# Gas_Sensor.net
KiCad netlist of a schematic drawn in EAGLE
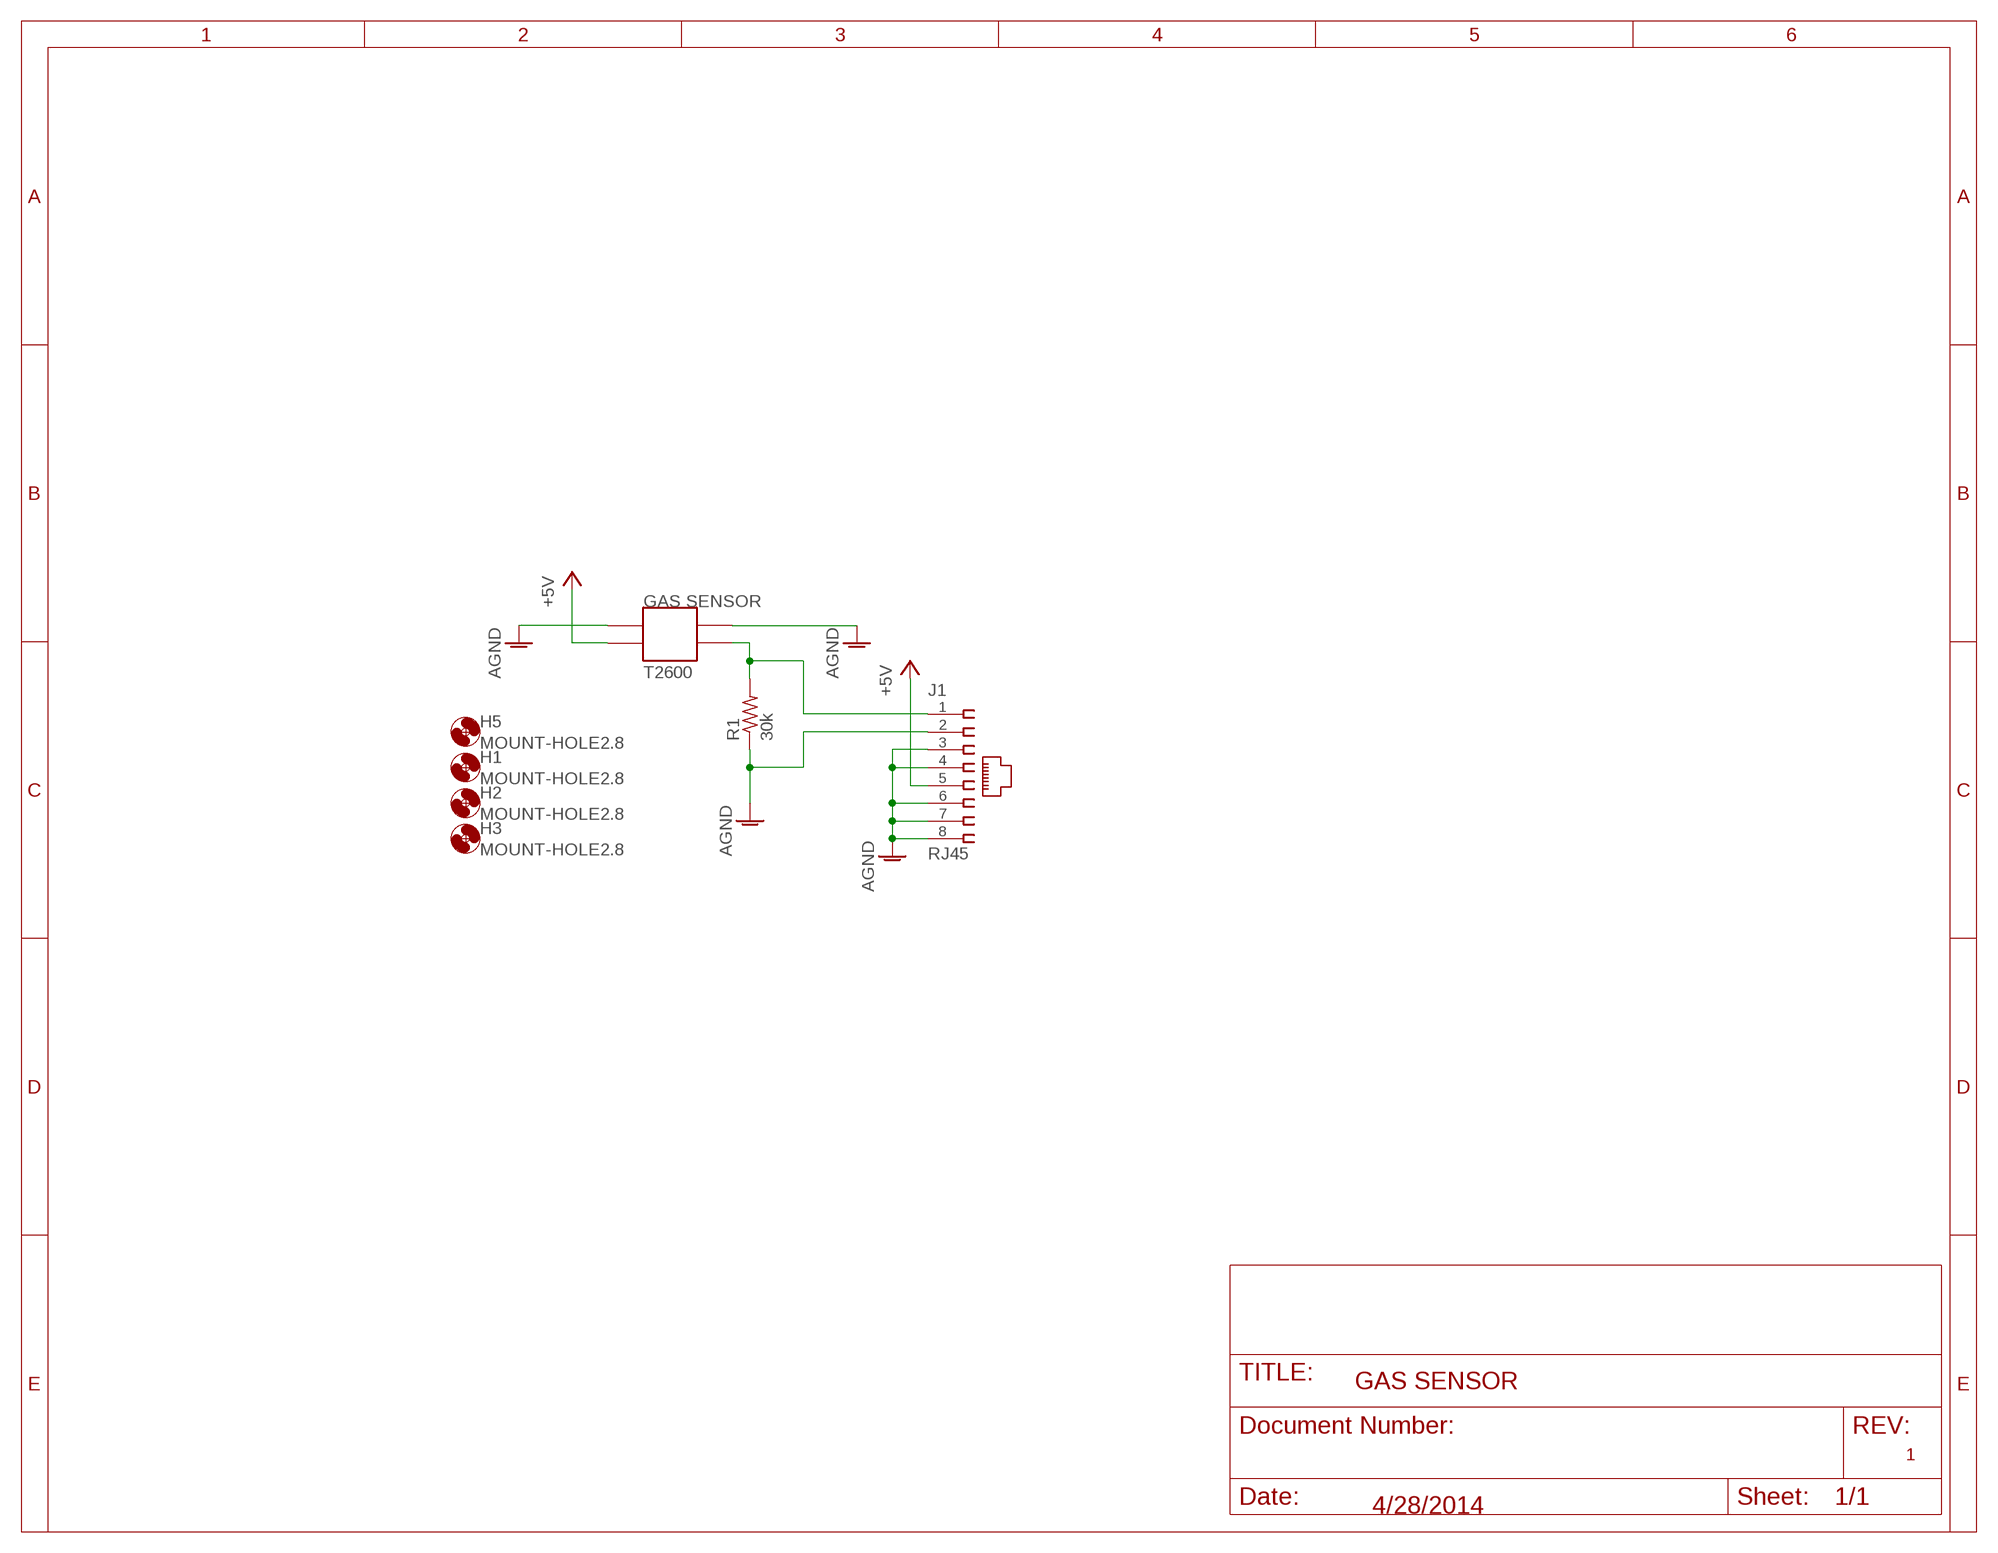
[diagram p0: schematic, sheet 1]

(export (version "E")
  (design (tool "Eeschema 10.0.6"))
  (components
    (comp (ref "H1")
      (value "MOUNT-HOLE2.8")
      (footprint "eagle-import:2,8")
      (libsource (lib "eagle-import") (part "MOUNT-HOLE2.8"))
    )
    (comp (ref "H2")
      (value "MOUNT-HOLE2.8")
      (footprint "eagle-import:2,8")
      (libsource (lib "eagle-import") (part "MOUNT-HOLE2.8"))
    )
    (comp (ref "H3")
      (value "MOUNT-HOLE2.8")
      (footprint "eagle-import:2,8")
      (libsource (lib "eagle-import") (part "MOUNT-HOLE2.8"))
    )
    (comp (ref "H5")
      (value "MOUNT-HOLE2.8")
      (footprint "eagle-import:2,8")
      (libsource (lib "eagle-import") (part "MOUNT-HOLE2.8"))
    )
    (comp (ref "J1")
      (value "RJ45")
      (footprint "eagle-import:555167-1")
      (libsource (lib "eagle-import") (part "555167-1"))
    )
    (comp (ref "R1")
      (value "30k")
      (footprint "eagle-import:R1206")
      (libsource (lib "eagle-import") (part "R-US_R1206"))
    )
    (comp (ref "U$1")
      (value "GAS_SENSOR")
      (footprint "eagle-import:GAS_SENSOR")
      (libsource (lib "eagle-import") (part "GAS_SENSOR"))
    )
  )
  (nets
    (net (code "1") (name "+5V") (class "Default")
      (node (ref "J1") (pin "5") (pinfunction "5_5") (pintype "passive"))
      (node (ref "U$1") (pin "P$3") (pinfunction "P$3_P$3") (pintype "bidirectional"))
    )
    (net (code "2") (name "AGND") (class "Default")
      (node (ref "J1") (pin "2") (pinfunction "2_2") (pintype "passive"))
      (node (ref "J1") (pin "3") (pinfunction "3_3") (pintype "passive"))
      (node (ref "J1") (pin "4") (pinfunction "4_4") (pintype "passive"))
      (node (ref "J1") (pin "6") (pinfunction "6_6") (pintype "passive"))
      (node (ref "J1") (pin "7") (pinfunction "7_7") (pintype "passive"))
      (node (ref "J1") (pin "8") (pinfunction "8_8") (pintype "passive"))
      (node (ref "R1") (pin "1") (pinfunction "1_1") (pintype "passive"))
      (node (ref "U$1") (pin "P$1") (pinfunction "P$4_P$1") (pintype "bidirectional"))
      (node (ref "U$1") (pin "P$2") (pinfunction "P$1_P$2") (pintype "bidirectional"))
    )
    (net (code "3") (name "Net-(U$1-P$2)") (class "Default")
      (node (ref "J1") (pin "1") (pinfunction "1_1") (pintype "passive"))
      (node (ref "R1") (pin "2") (pinfunction "2_2") (pintype "passive"))
      (node (ref "U$1") (pin "P$4") (pinfunction "P$2_P$4") (pintype "bidirectional"))
    )
  )
)
